# DroneMainBoard.net
KiCad netlist of a schematic drawn in EAGLE
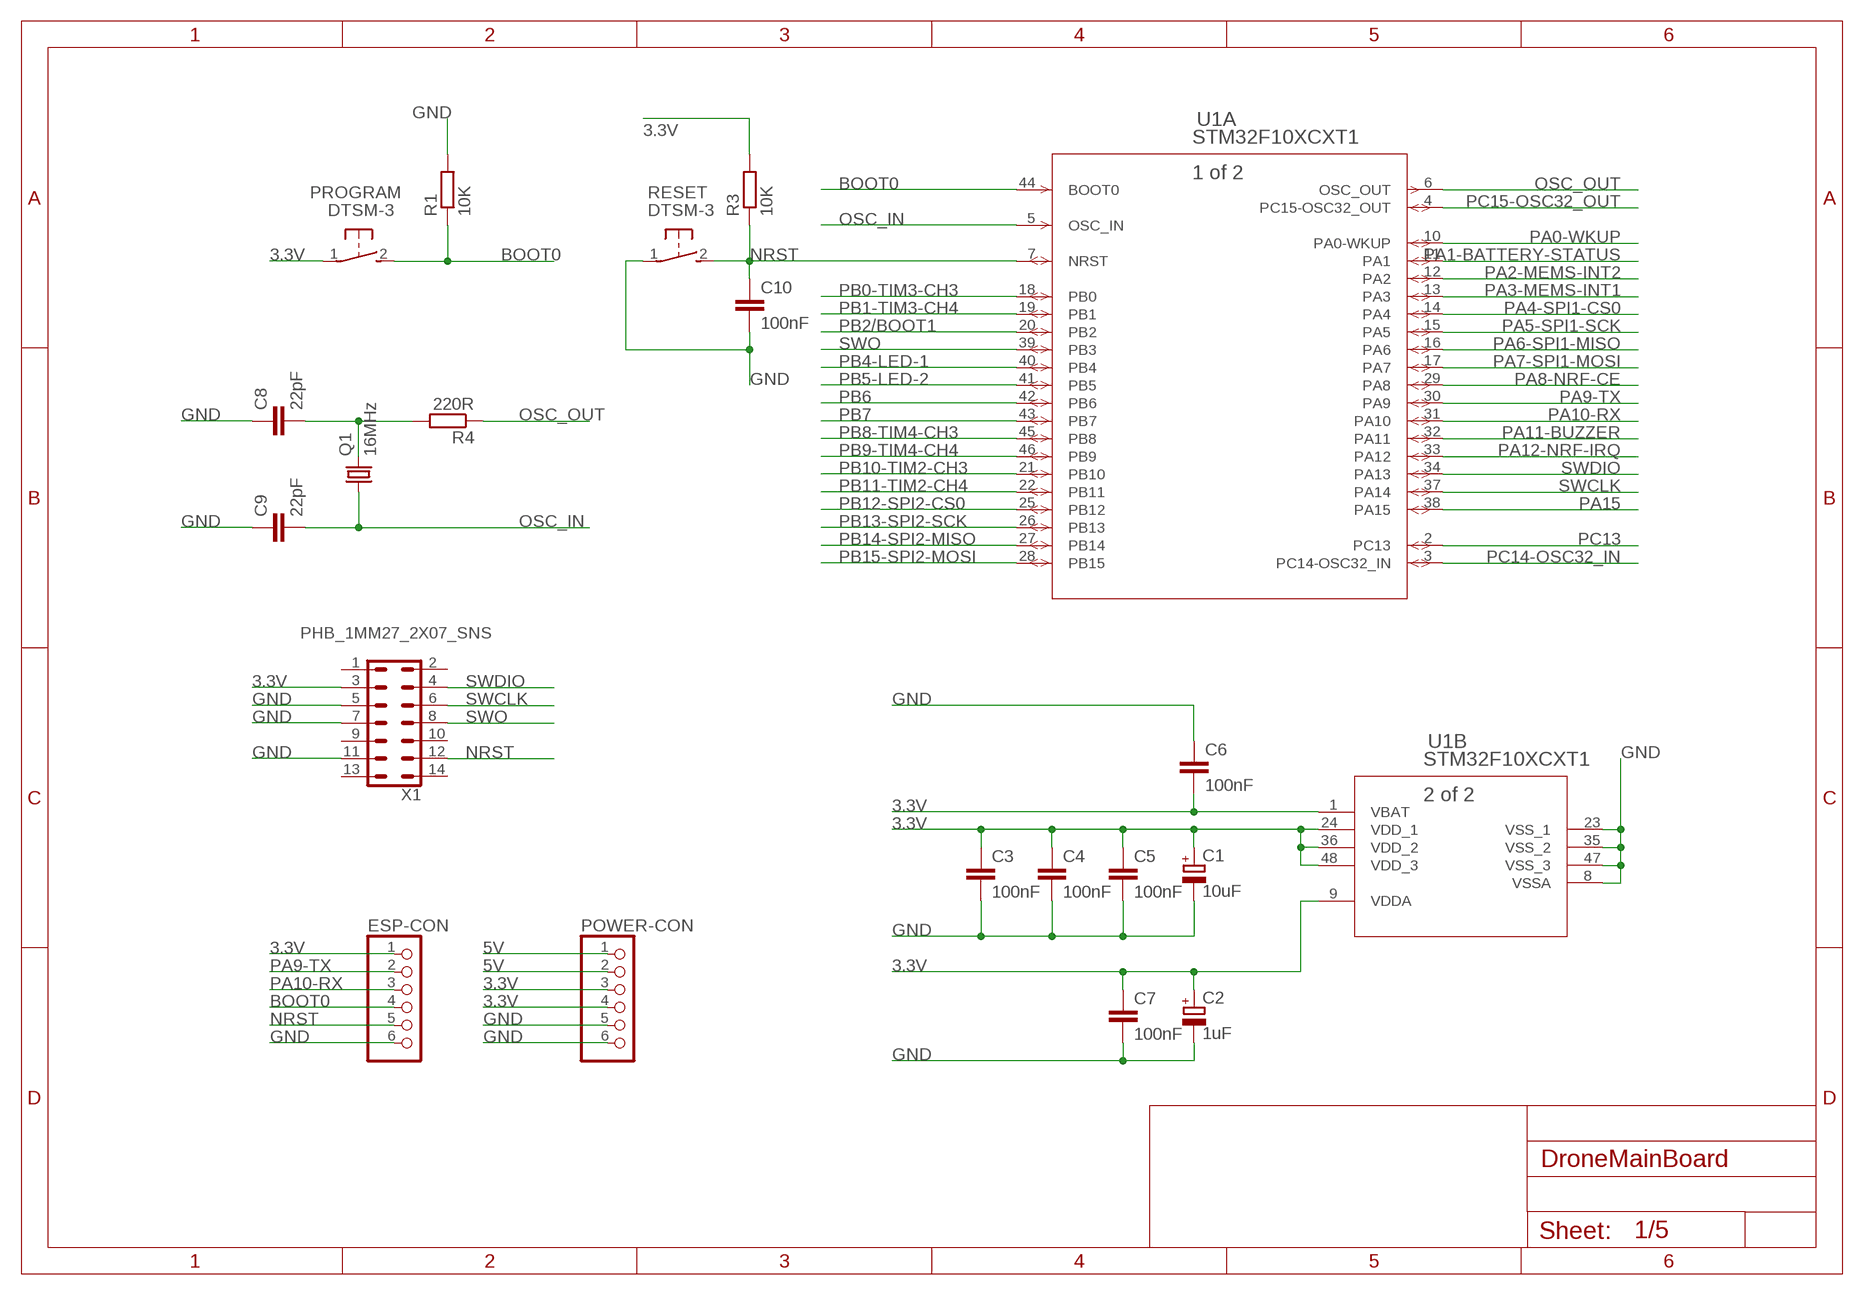
[diagram p0: schematic, sheet 1]
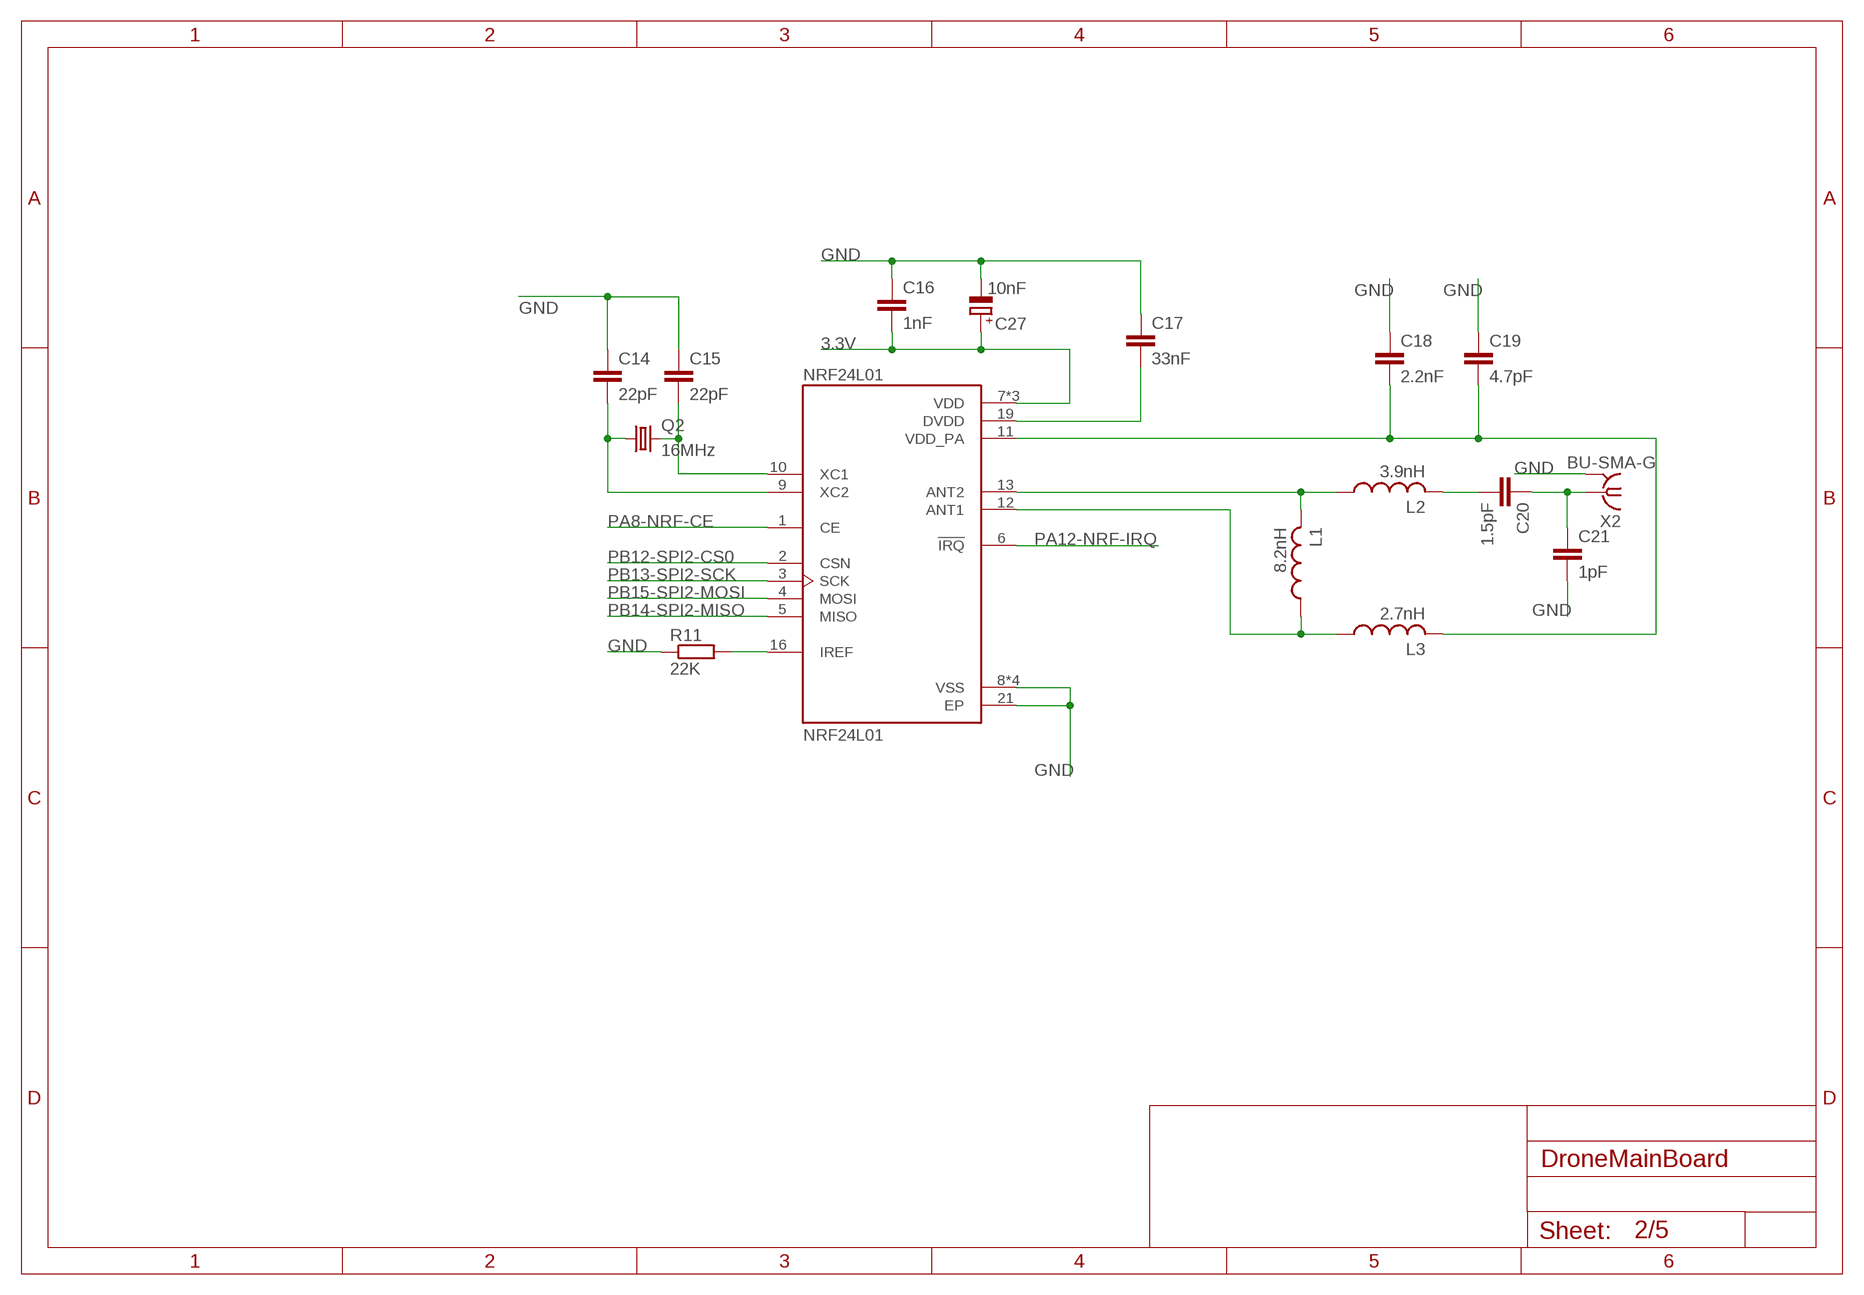
[diagram p1: schematic, sheet 2]
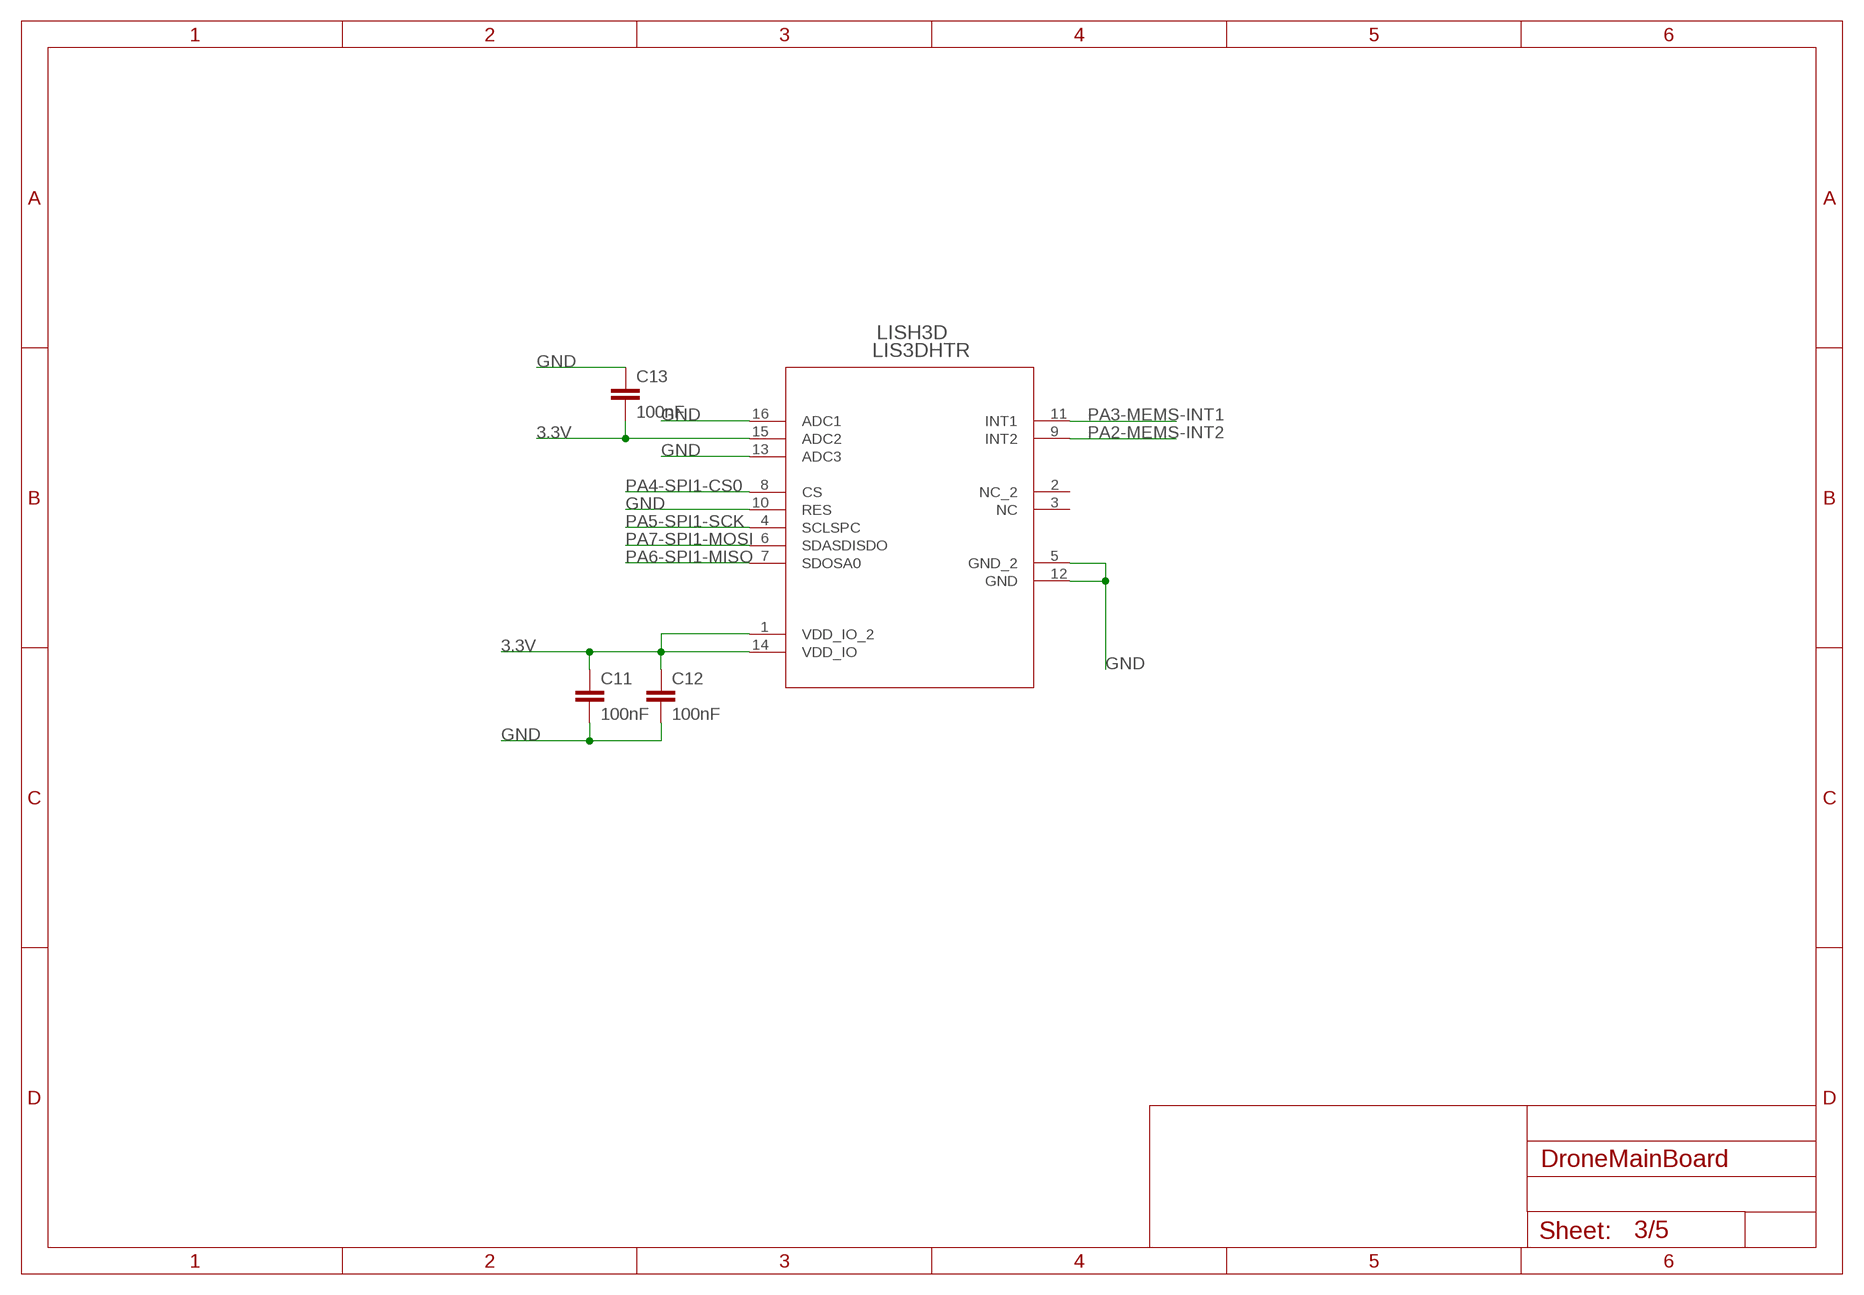
[diagram p2: schematic, sheet 3]
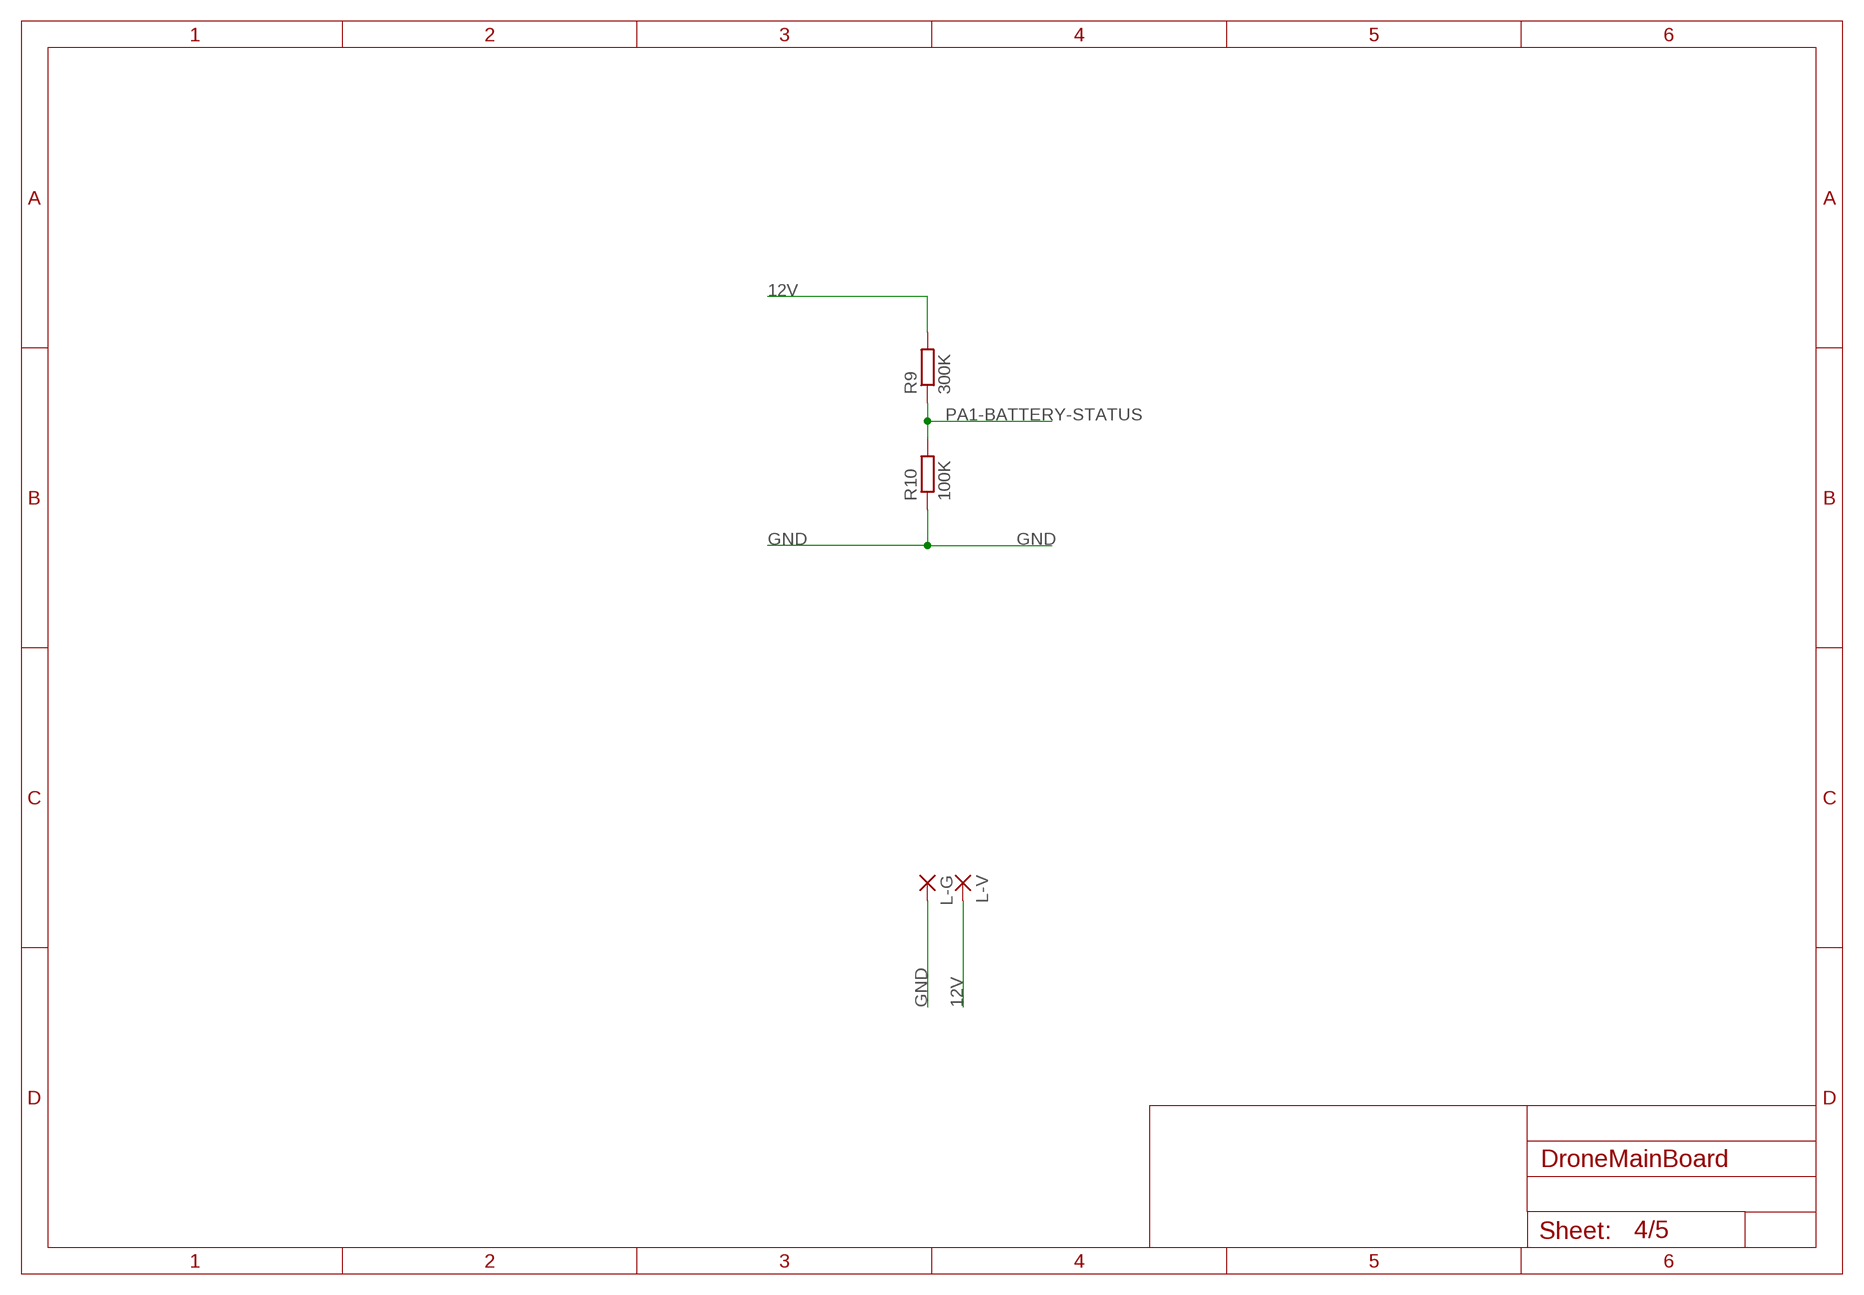
[diagram p3: schematic, sheet 4]
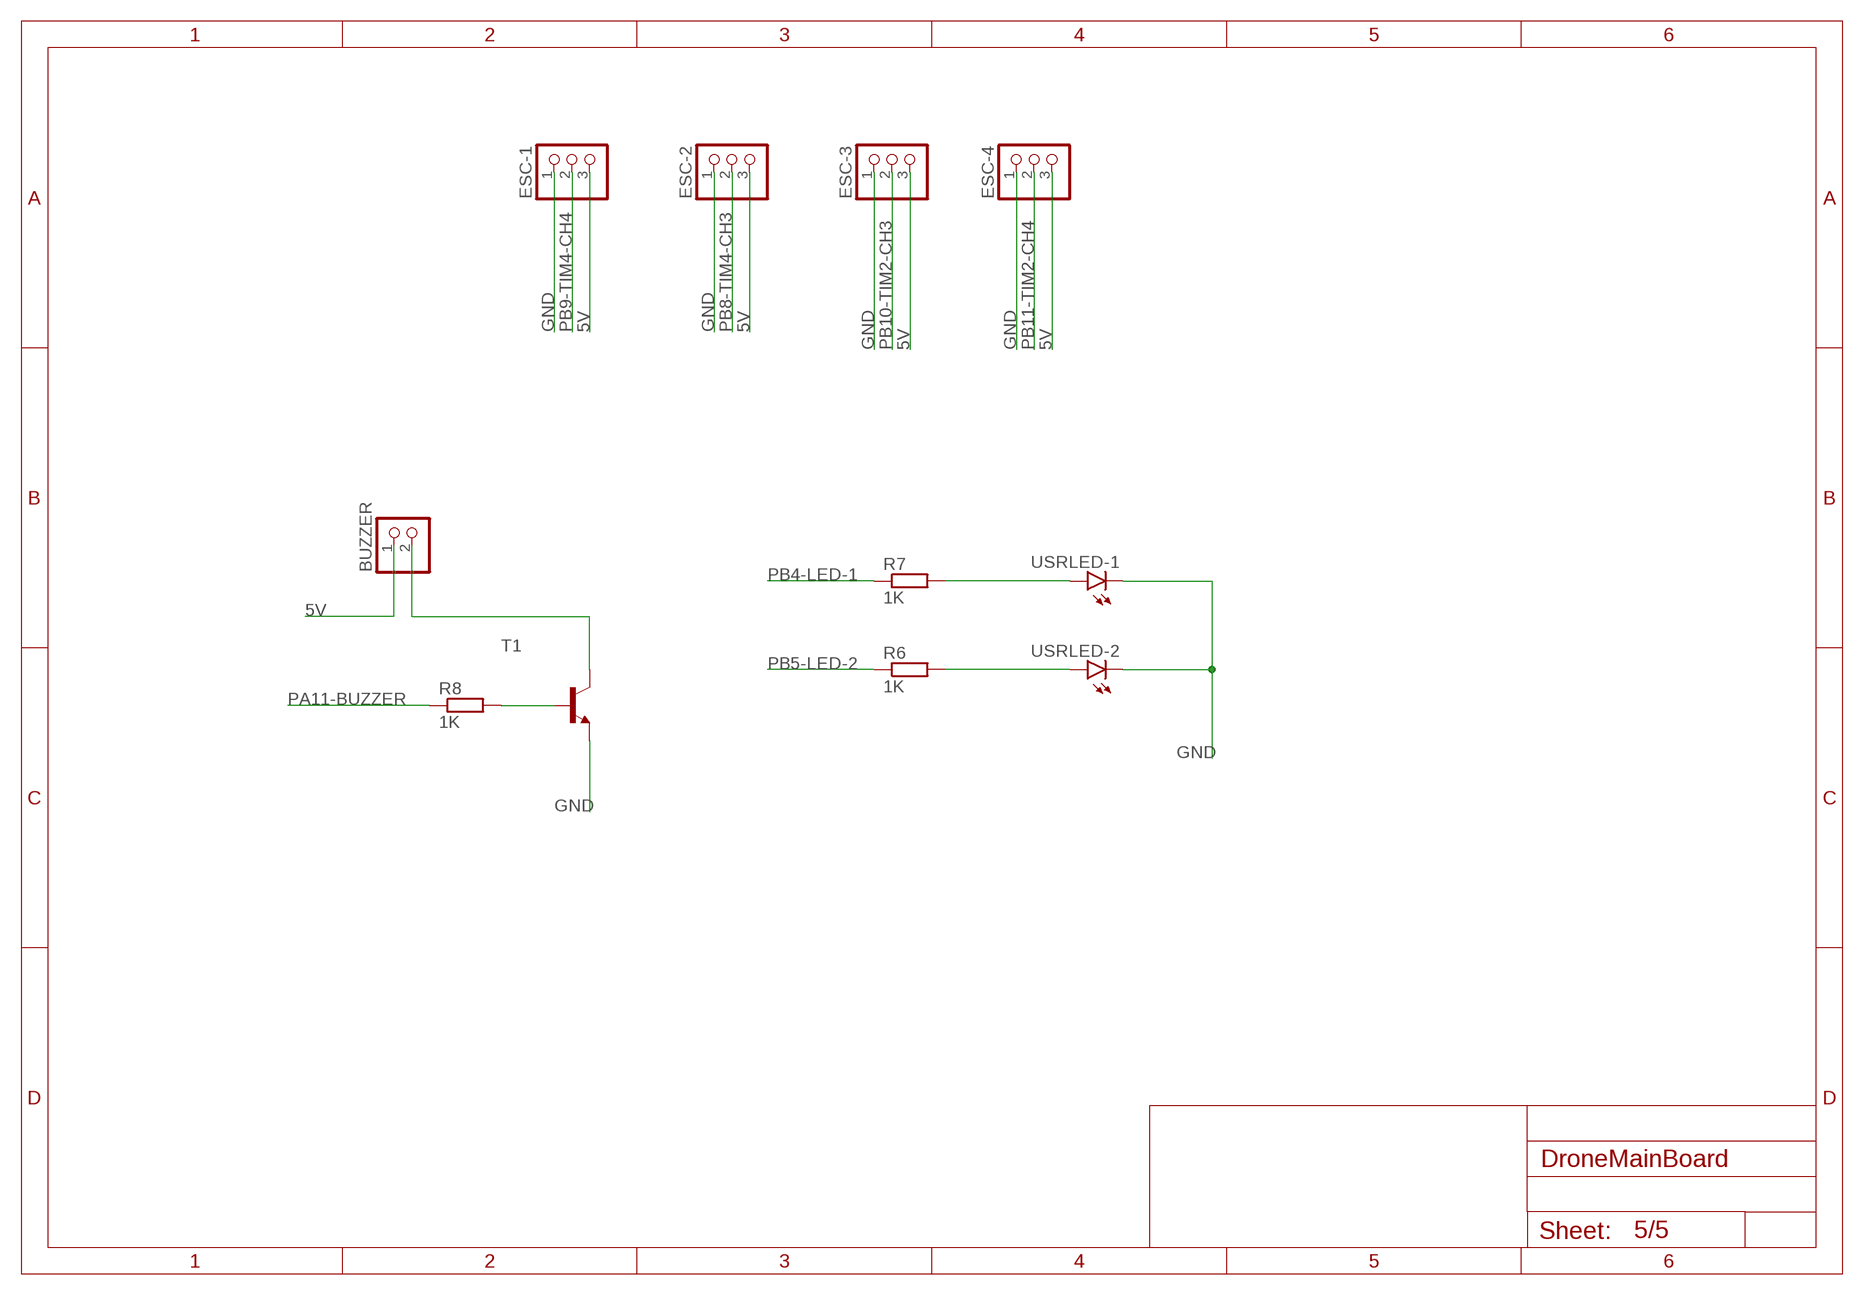
[diagram p4: schematic, sheet 5]

(export (version "E")
  (design (tool "Eeschema 10.0.6"))
  (components
    (comp (ref "C1")
      (value "10uF")
      (footprint "eagle-import:SMC_A")
      (libsource (lib "eagle-import") (part "CPOL-EUSMCA"))
    )
    (comp (ref "C2")
      (value "1uF")
      (footprint "eagle-import:SMC_A")
      (libsource (lib "eagle-import") (part "CPOL-EUSMCA"))
    )
    (comp (ref "C3")
      (value "100nF")
      (footprint "eagle-import:C0603")
      (libsource (lib "eagle-import") (part "C-EUC0603"))
    )
    (comp (ref "C4")
      (value "100nF")
      (footprint "eagle-import:C0603")
      (libsource (lib "eagle-import") (part "C-EUC0603"))
    )
    (comp (ref "C5")
      (value "100nF")
      (footprint "eagle-import:C0603")
      (libsource (lib "eagle-import") (part "C-EUC0603"))
    )
    (comp (ref "C6")
      (value "100nF")
      (footprint "eagle-import:C0603")
      (libsource (lib "eagle-import") (part "C-EUC0603"))
    )
    (comp (ref "C7")
      (value "100nF")
      (footprint "eagle-import:C0603")
      (libsource (lib "eagle-import") (part "C-EUC0603"))
    )
    (comp (ref "C8")
      (value "22pF")
      (footprint "eagle-import:C0603")
      (libsource (lib "eagle-import") (part "C-EUC0603"))
    )
    (comp (ref "C9")
      (value "22pF")
      (footprint "eagle-import:C0603")
      (libsource (lib "eagle-import") (part "C-EUC0603"))
    )
    (comp (ref "C10")
      (value "100nF")
      (footprint "eagle-import:C0603")
      (libsource (lib "eagle-import") (part "C-EUC0603"))
    )
    (comp (ref "ESP-CON")
      (value "PINHD-1X6")
      (footprint "eagle-import:1X06")
      (libsource (lib "eagle-import") (part "PINHD-1X6"))
    )
    (comp (ref "POWER-CON")
      (value "PINHD-1X6")
      (footprint "eagle-import:1X06")
      (libsource (lib "eagle-import") (part "PINHD-1X6"))
    )
    (comp (ref "PROGRAM")
      (value "DTSM-3")
      (footprint "eagle-import:DTSM-3")
      (libsource (lib "eagle-import") (part "DTSM-3"))
    )
    (comp (ref "Q1")
      (value "16MHz")
      (footprint "eagle-import:HC49_S")
      (libsource (lib "eagle-import") (part "CRYSTALHC49S"))
    )
    (comp (ref "R1")
      (value "10K")
      (footprint "eagle-import:R0603")
      (libsource (lib "eagle-import") (part "R-EU_R0603"))
    )
    (comp (ref "R3")
      (value "10K")
      (footprint "eagle-import:R0603")
      (libsource (lib "eagle-import") (part "R-EU_R0603"))
    )
    (comp (ref "R4")
      (value "220R")
      (footprint "eagle-import:R0603")
      (libsource (lib "eagle-import") (part "R-EU_R0603"))
    )
    (comp (ref "RESET")
      (value "DTSM-3")
      (footprint "eagle-import:DTSM-3")
      (libsource (lib "eagle-import") (part "DTSM-3"))
    )
    (comp (ref "U1")
      (value "STM32F10XCXT1")
      (footprint "eagle-import:LQFP48-7X7MM")
      (fields (field (name "COPYRIGHT") "Copyright (C) 2016 Accelerated Designs. All rights reserved"))
      (libsource (lib "eagle-import") (part "STM32F10XCXT1"))
    )
    (comp (ref "X1")
      (value "PHB_1MM27_2X07_SNS")
      (footprint "eagle-import:PHB_1MM27_2X07_SNS")
      (libsource (lib "eagle-import") (part "PHB_1MM27_2X07_SNS"))
    )
    (comp (ref "C11")
      (value "100nF")
      (footprint "eagle-import:C0603")
      (libsource (lib "eagle-import") (part "C-EUC0603"))
    )
    (comp (ref "C12")
      (value "100nF")
      (footprint "eagle-import:C0603")
      (libsource (lib "eagle-import") (part "C-EUC0603"))
    )
    (comp (ref "C13")
      (value "100nF")
      (footprint "eagle-import:C0603")
      (libsource (lib "eagle-import") (part "C-EUC0603"))
    )
    (comp (ref "LISH3D")
      (value "LIS3DHTR")
      (footprint "eagle-import:LGA-16_3X3X1MM_STM")
      (libsource (lib "eagle-import") (part "LIS3DHTR"))
    )
    (comp (ref "C14")
      (value "22pF")
      (footprint "eagle-import:C0603")
      (libsource (lib "eagle-import") (part "C-EUC0603"))
    )
    (comp (ref "C15")
      (value "22pF")
      (footprint "eagle-import:C0603")
      (libsource (lib "eagle-import") (part "C-EUC0603"))
    )
    (comp (ref "C16")
      (value "1nF")
      (footprint "eagle-import:C0603")
      (libsource (lib "eagle-import") (part "C-EUC0603"))
    )
    (comp (ref "C17")
      (value "33nF")
      (footprint "eagle-import:C0603")
      (libsource (lib "eagle-import") (part "C-EUC0603"))
    )
    (comp (ref "C18")
      (value "2.2nF")
      (footprint "eagle-import:C0603")
      (libsource (lib "eagle-import") (part "C-EUC0603"))
    )
    (comp (ref "C19")
      (value "4.7pF")
      (footprint "eagle-import:C0603")
      (libsource (lib "eagle-import") (part "C-EUC0603"))
    )
    (comp (ref "C20")
      (value "1.5pF")
      (footprint "eagle-import:C0603")
      (libsource (lib "eagle-import") (part "C-EUC0603"))
    )
    (comp (ref "C21")
      (value "1pF")
      (footprint "eagle-import:C0603")
      (libsource (lib "eagle-import") (part "C-EUC0603"))
    )
    (comp (ref "C27")
      (value "10nF")
      (footprint "eagle-import:SMC_A")
      (libsource (lib "eagle-import") (part "CPOL-EUSMCA"))
    )
    (comp (ref "L1")
      (value "8.2nH")
      (footprint "eagle-import:L2012C")
      (libsource (lib "eagle-import") (part "L-USL2012C"))
    )
    (comp (ref "L2")
      (value "3.9nH")
      (footprint "eagle-import:L2012C")
      (libsource (lib "eagle-import") (part "L-USL2012C"))
    )
    (comp (ref "L3")
      (value "2.7nH")
      (footprint "eagle-import:L2012C")
      (libsource (lib "eagle-import") (part "L-USL2012C"))
    )
    (comp (ref "NRF24L01")
      (value "NRF24L01")
      (footprint "eagle-import:QFN50P400X400X95-21N")
      (fields (field (name "MF") "Nordic"))
      (libsource (lib "eagle-import") (part "NRF24L01"))
    )
    (comp (ref "Q2")
      (value "16MHz")
      (footprint "eagle-import:HC49_S")
      (libsource (lib "eagle-import") (part "CRYSTALHC49S"))
    )
    (comp (ref "R11")
      (value "22K")
      (footprint "eagle-import:R0603")
      (libsource (lib "eagle-import") (part "R-EU_R0603"))
    )
    (comp (ref "X2")
      (value "BU-SMA-G")
      (footprint "eagle-import:BU-SMA-G")
      (libsource (lib "eagle-import") (part "BU-SMA-G"))
    )
    (comp (ref "L-G")
      (value "2,54/1,1")
      (footprint "eagle-import:2,54_1,1")
      (libsource (lib "eagle-import") (part "2,54/1,1"))
    )
    (comp (ref "L-V")
      (value "2,54/1,1")
      (footprint "eagle-import:2,54_1,1")
      (libsource (lib "eagle-import") (part "2,54/1,1"))
    )
    (comp (ref "R9")
      (value "300K")
      (footprint "eagle-import:R0603")
      (libsource (lib "eagle-import") (part "R-EU_R0603"))
    )
    (comp (ref "R10")
      (value "100K")
      (footprint "eagle-import:R0603")
      (libsource (lib "eagle-import") (part "R-EU_R0603"))
    )
    (comp (ref "BUZZER")
      (value "PINHD-1X2")
      (footprint "eagle-import:1X02")
      (libsource (lib "eagle-import") (part "PINHD-1X2"))
    )
    (comp (ref "ESC-1")
      (value "PINHD-1X3")
      (footprint "eagle-import:1X03")
      (libsource (lib "eagle-import") (part "PINHD-1X3"))
    )
    (comp (ref "ESC-2")
      (value "PINHD-1X3")
      (footprint "eagle-import:1X03")
      (libsource (lib "eagle-import") (part "PINHD-1X3"))
    )
    (comp (ref "ESC-3")
      (value "PINHD-1X3")
      (footprint "eagle-import:1X03")
      (libsource (lib "eagle-import") (part "PINHD-1X3"))
    )
    (comp (ref "ESC-4")
      (value "PINHD-1X3")
      (footprint "eagle-import:1X03")
      (libsource (lib "eagle-import") (part "PINHD-1X3"))
    )
    (comp (ref "R6")
      (value "1K")
      (footprint "eagle-import:R0603")
      (libsource (lib "eagle-import") (part "R-EU_R0603"))
    )
    (comp (ref "R7")
      (value "1K")
      (footprint "eagle-import:R0603")
      (libsource (lib "eagle-import") (part "R-EU_R0603"))
    )
    (comp (ref "R8")
      (value "1K")
      (footprint "eagle-import:R0603")
      (libsource (lib "eagle-import") (part "R-EU_R0603"))
    )
    (comp (ref "T1")
      (value "MMBT3904LT1-NPN-SOT23-BEC")
      (footprint "eagle-import:SOT23-BEC")
      (libsource (lib "eagle-import") (part "-NPN-SOT23-BECMMBT3904LT1"))
    )
    (comp (ref "USRLED-1")
      (value "LEDCHIP-LED0805")
      (footprint "eagle-import:CHIP-LED0805")
      (libsource (lib "eagle-import") (part "LEDCHIP-LED0805"))
    )
    (comp (ref "USRLED-2")
      (value "LEDCHIP-LED0805")
      (footprint "eagle-import:CHIP-LED0805")
      (libsource (lib "eagle-import") (part "LEDCHIP-LED0805"))
    )
  )
  (nets
    (net (code "1") (name "3.3V") (class "Default")
      (node (ref "C1") (pin "+") (pinfunction "+_+") (pintype "passive"))
      (node (ref "C11") (pin "1") (pinfunction "1_1") (pintype "passive"))
      (node (ref "C12") (pin "1") (pinfunction "1_1") (pintype "passive"))
      (node (ref "C13") (pin "2") (pinfunction "2_2") (pintype "passive"))
      (node (ref "C16") (pin "2") (pinfunction "2_2") (pintype "passive"))
      (node (ref "C2") (pin "+") (pinfunction "+_+") (pintype "passive"))
      (node (ref "C27") (pin "+") (pinfunction "+_+") (pintype "passive"))
      (node (ref "C3") (pin "1") (pinfunction "1_1") (pintype "passive"))
      (node (ref "C4") (pin "1") (pinfunction "1_1") (pintype "passive"))
      (node (ref "C5") (pin "1") (pinfunction "1_1") (pintype "passive"))
      (node (ref "C6") (pin "2") (pinfunction "2_2") (pintype "passive"))
      (node (ref "C7") (pin "1") (pinfunction "1_1") (pintype "passive"))
      (node (ref "ESP-CON") (pin "1") (pinfunction "1_1") (pintype "passive"))
      (node (ref "LISH3D") (pin "1") (pinfunction "VDD_IO_2_1") (pintype "power_in"))
      (node (ref "LISH3D") (pin "14") (pinfunction "VDD_IO_14") (pintype "power_in"))
      (node (ref "LISH3D") (pin "15") (pinfunction "ADC2_15") (pintype "input"))
      (node (ref "NRF24L01") (pin "15") (pinfunction "VDD_15") (pintype "power_in"))
      (node (ref "NRF24L01") (pin "18") (pinfunction "VDD_18") (pintype "power_in"))
      (node (ref "NRF24L01") (pin "7") (pinfunction "VDD_7") (pintype "power_in"))
      (node (ref "POWER-CON") (pin "3") (pinfunction "3_3") (pintype "passive"))
      (node (ref "POWER-CON") (pin "4") (pinfunction "4_4") (pintype "passive"))
      (node (ref "PROGRAM") (pin "1") (pinfunction "1_1") (pintype "passive"))
      (node (ref "R3") (pin "2") (pinfunction "2_2") (pintype "passive"))
      (node (ref "U1") (pin "1") (pinfunction "VBAT_1") (pintype "power_in"))
      (node (ref "U1") (pin "24") (pinfunction "VDD_1_24") (pintype "power_in"))
      (node (ref "U1") (pin "36") (pinfunction "VDD_2_36") (pintype "power_in"))
      (node (ref "U1") (pin "48") (pinfunction "VDD_3_48") (pintype "power_in"))
      (node (ref "U1") (pin "9") (pinfunction "VDDA_9") (pintype "power_in"))
      (node (ref "X1") (pin "3") (pinfunction "3_3") (pintype "passive"))
    )
    (net (code "2") (name "5V") (class "Default")
      (node (ref "BUZZER") (pin "1") (pinfunction "1_1") (pintype "passive"))
      (node (ref "ESC-1") (pin "3") (pinfunction "3_3") (pintype "passive"))
      (node (ref "ESC-2") (pin "3") (pinfunction "3_3") (pintype "passive"))
      (node (ref "ESC-3") (pin "3") (pinfunction "3_3") (pintype "passive"))
      (node (ref "ESC-4") (pin "3") (pinfunction "3_3") (pintype "passive"))
      (node (ref "POWER-CON") (pin "1") (pinfunction "1_1") (pintype "passive"))
      (node (ref "POWER-CON") (pin "2") (pinfunction "2_2") (pintype "passive"))
    )
    (net (code "3") (name "12V") (class "Default")
      (node (ref "L-V") (pin "1") (pinfunction "P_1") (pintype "passive"))
      (node (ref "R9") (pin "2") (pinfunction "2_2") (pintype "passive"))
    )
    (net (code "4") (name "BOOT0") (class "Default")
      (node (ref "ESP-CON") (pin "4") (pinfunction "4_4") (pintype "passive"))
      (node (ref "PROGRAM") (pin "2") (pinfunction "2_2") (pintype "passive"))
      (node (ref "R1") (pin "1") (pinfunction "1_1") (pintype "passive"))
      (node (ref "U1") (pin "44") (pinfunction "BOOT0_44") (pintype "input"))
    )
    (net (code "5") (name "GND") (class "Default")
      (node (ref "C1") (pin "-") (pinfunction "-_-") (pintype "passive"))
      (node (ref "C10") (pin "2") (pinfunction "2_2") (pintype "passive"))
      (node (ref "C11") (pin "2") (pinfunction "2_2") (pintype "passive"))
      (node (ref "C12") (pin "2") (pinfunction "2_2") (pintype "passive"))
      (node (ref "C13") (pin "1") (pinfunction "1_1") (pintype "passive"))
      (node (ref "C14") (pin "1") (pinfunction "1_1") (pintype "passive"))
      (node (ref "C15") (pin "1") (pinfunction "1_1") (pintype "passive"))
      (node (ref "C16") (pin "1") (pinfunction "1_1") (pintype "passive"))
      (node (ref "C17") (pin "1") (pinfunction "1_1") (pintype "passive"))
      (node (ref "C18") (pin "1") (pinfunction "1_1") (pintype "passive"))
      (node (ref "C19") (pin "1") (pinfunction "1_1") (pintype "passive"))
      (node (ref "C2") (pin "-") (pinfunction "-_-") (pintype "passive"))
      (node (ref "C21") (pin "2") (pinfunction "2_2") (pintype "passive"))
      (node (ref "C27") (pin "-") (pinfunction "-_-") (pintype "passive"))
      (node (ref "C3") (pin "2") (pinfunction "2_2") (pintype "passive"))
      (node (ref "C4") (pin "2") (pinfunction "2_2") (pintype "passive"))
      (node (ref "C5") (pin "2") (pinfunction "2_2") (pintype "passive"))
      (node (ref "C6") (pin "1") (pinfunction "1_1") (pintype "passive"))
      (node (ref "C7") (pin "2") (pinfunction "2_2") (pintype "passive"))
      (node (ref "C8") (pin "1") (pinfunction "1_1") (pintype "passive"))
      (node (ref "C9") (pin "1") (pinfunction "1_1") (pintype "passive"))
      (node (ref "ESC-1") (pin "1") (pinfunction "1_1") (pintype "passive"))
      (node (ref "ESC-2") (pin "1") (pinfunction "1_1") (pintype "passive"))
      (node (ref "ESC-3") (pin "1") (pinfunction "1_1") (pintype "passive"))
      (node (ref "ESC-4") (pin "1") (pinfunction "1_1") (pintype "passive"))
      (node (ref "ESP-CON") (pin "6") (pinfunction "6_6") (pintype "passive"))
      (node (ref "L-G") (pin "1") (pinfunction "P_1") (pintype "passive"))
      (node (ref "LISH3D") (pin "10") (pinfunction "RES_10") (pintype "passive"))
      (node (ref "LISH3D") (pin "12") (pinfunction "GND_12") (pintype "power_in"))
      (node (ref "LISH3D") (pin "13") (pinfunction "ADC3_13") (pintype "input"))
      (node (ref "LISH3D") (pin "16") (pinfunction "ADC1_16") (pintype "input"))
      (node (ref "LISH3D") (pin "5") (pinfunction "GND_2_5") (pintype "power_in"))
      (node (ref "NRF24L01") (pin "14") (pinfunction "VSS_14") (pintype "power_in"))
      (node (ref "NRF24L01") (pin "17") (pinfunction "VSS_17") (pintype "power_in"))
      (node (ref "NRF24L01") (pin "20") (pinfunction "VSS_20") (pintype "power_in"))
      (node (ref "NRF24L01") (pin "21") (pinfunction "EP_21") (pintype "power_in"))
      (node (ref "NRF24L01") (pin "8") (pinfunction "VSS_8") (pintype "power_in"))
      (node (ref "POWER-CON") (pin "5") (pinfunction "5_5") (pintype "passive"))
      (node (ref "POWER-CON") (pin "6") (pinfunction "6_6") (pintype "passive"))
      (node (ref "R1") (pin "2") (pinfunction "2_2") (pintype "passive"))
      (node (ref "R10") (pin "1") (pinfunction "1_1") (pintype "passive"))
      (node (ref "R11") (pin "1") (pinfunction "1_1") (pintype "passive"))
      (node (ref "RESET") (pin "1") (pinfunction "1_1") (pintype "passive"))
      (node (ref "T1") (pin "E") (pinfunction "E_E") (pintype "passive"))
      (node (ref "U1") (pin "23") (pinfunction "VSS_1_23") (pintype "power_in"))
      (node (ref "U1") (pin "35") (pinfunction "VSS_2_35") (pintype "power_in"))
      (node (ref "U1") (pin "47") (pinfunction "VSS_3_47") (pintype "power_in"))
      (node (ref "U1") (pin "8") (pinfunction "VSSA_8") (pintype "power_in"))
      (node (ref "USRLED-1") (pin "C") (pinfunction "C_C") (pintype "passive"))
      (node (ref "USRLED-2") (pin "C") (pinfunction "C_C") (pintype "passive"))
      (node (ref "X1") (pin "11") (pinfunction "11_11") (pintype "passive"))
      (node (ref "X1") (pin "5") (pinfunction "5_5") (pintype "passive"))
      (node (ref "X1") (pin "7") (pinfunction "7_7") (pintype "passive"))
      (node (ref "X2") (pin "2") (pinfunction "2_2") (pintype "passive"))
      (node (ref "X2") (pin "3") (pinfunction "2_3") (pintype "passive"))
      (node (ref "X2") (pin "4") (pinfunction "2_4") (pintype "passive"))
      (node (ref "X2") (pin "5") (pinfunction "2_5") (pintype "passive"))
    )
    (net (code "6") (name "NRST") (class "Default")
      (node (ref "C10") (pin "1") (pinfunction "1_1") (pintype "passive"))
      (node (ref "ESP-CON") (pin "5") (pinfunction "5_5") (pintype "passive"))
      (node (ref "R3") (pin "1") (pinfunction "1_1") (pintype "passive"))
      (node (ref "RESET") (pin "2") (pinfunction "2_2") (pintype "passive"))
      (node (ref "U1") (pin "7") (pinfunction "NRST_7") (pintype "bidirectional"))
      (node (ref "X1") (pin "12") (pinfunction "12_12") (pintype "passive"))
    )
    (net (code "7") (name "Net-(BUZZER-Pad2)") (class "Default")
      (node (ref "BUZZER") (pin "2") (pinfunction "2_2") (pintype "passive"))
      (node (ref "T1") (pin "C") (pinfunction "C_C") (pintype "passive"))
    )
    (net (code "8") (name "Net-(C8-Pad2)") (class "Default")
      (node (ref "C8") (pin "2") (pinfunction "2_2") (pintype "passive"))
      (node (ref "Q1") (pin "2") (pinfunction "2_2") (pintype "passive"))
      (node (ref "R4") (pin "2") (pinfunction "2_2") (pintype "passive"))
    )
    (net (code "9") (name "Net-(C20-Pad1)") (class "Default")
      (node (ref "C20") (pin "1") (pinfunction "1_1") (pintype "passive"))
      (node (ref "C21") (pin "1") (pinfunction "1_1") (pintype "passive"))
      (node (ref "X2") (pin "1") (pinfunction "1_1") (pintype "passive"))
    )
    (net (code "10") (name "Net-(C20-Pad2)") (class "Default")
      (node (ref "C20") (pin "2") (pinfunction "2_2") (pintype "passive"))
      (node (ref "L2") (pin "2") (pinfunction "2_2") (pintype "passive"))
    )
    (net (code "11") (name "Net-(NRF24L01-ANT1)") (class "Default")
      (node (ref "L1") (pin "1") (pinfunction "1_1") (pintype "passive"))
      (node (ref "L3") (pin "1") (pinfunction "1_1") (pintype "passive"))
      (node (ref "NRF24L01") (pin "12") (pinfunction "ANT1_12") (pintype "bidirectional"))
    )
    (net (code "12") (name "Net-(NRF24L01-ANT2)") (class "Default")
      (node (ref "L1") (pin "2") (pinfunction "2_2") (pintype "passive"))
      (node (ref "L2") (pin "1") (pinfunction "1_1") (pintype "passive"))
      (node (ref "NRF24L01") (pin "13") (pinfunction "ANT2_13") (pintype "bidirectional"))
    )
    (net (code "13") (name "Net-(NRF24L01-DVDD)") (class "Default")
      (node (ref "C17") (pin "2") (pinfunction "2_2") (pintype "passive"))
      (node (ref "NRF24L01") (pin "19") (pinfunction "DVDD_19") (pintype "power_in"))
    )
    (net (code "14") (name "Net-(NRF24L01-IREF)") (class "Default")
      (node (ref "NRF24L01") (pin "16") (pinfunction "IREF_16") (pintype "input"))
      (node (ref "R11") (pin "2") (pinfunction "2_2") (pintype "passive"))
    )
    (net (code "15") (name "Net-(NRF24L01-VDD_PA)") (class "Default")
      (node (ref "C18") (pin "2") (pinfunction "2_2") (pintype "passive"))
      (node (ref "C19") (pin "2") (pinfunction "2_2") (pintype "passive"))
      (node (ref "L3") (pin "2") (pinfunction "2_2") (pintype "passive"))
      (node (ref "NRF24L01") (pin "11") (pinfunction "VDD_PA_11") (pintype "power_in"))
    )
    (net (code "16") (name "Net-(NRF24L01-XC1)") (class "Default")
      (node (ref "C15") (pin "2") (pinfunction "2_2") (pintype "passive"))
      (node (ref "NRF24L01") (pin "10") (pinfunction "XC1_10") (pintype "input"))
      (node (ref "Q2") (pin "2") (pinfunction "2_2") (pintype "passive"))
    )
    (net (code "17") (name "Net-(NRF24L01-XC2)") (class "Default")
      (node (ref "C14") (pin "2") (pinfunction "2_2") (pintype "passive"))
      (node (ref "NRF24L01") (pin "9") (pinfunction "XC2_9") (pintype "output"))
      (node (ref "Q2") (pin "1") (pinfunction "1_1") (pintype "passive"))
    )
    (net (code "18") (name "Net-(R6-Pad2)") (class "Default")
      (node (ref "R6") (pin "2") (pinfunction "2_2") (pintype "passive"))
      (node (ref "USRLED-2") (pin "A") (pinfunction "A_A") (pintype "passive"))
    )
    (net (code "19") (name "Net-(R7-Pad2)") (class "Default")
      (node (ref "R7") (pin "2") (pinfunction "2_2") (pintype "passive"))
      (node (ref "USRLED-1") (pin "A") (pinfunction "A_A") (pintype "passive"))
    )
    (net (code "20") (name "Net-(R8-Pad2)") (class "Default")
      (node (ref "R8") (pin "2") (pinfunction "2_2") (pintype "passive"))
      (node (ref "T1") (pin "B") (pinfunction "B_B") (pintype "passive"))
    )
    (net (code "21") (name "OSC_IN") (class "Default")
      (node (ref "C9") (pin "2") (pinfunction "2_2") (pintype "passive"))
      (node (ref "Q1") (pin "1") (pinfunction "1_1") (pintype "passive"))
      (node (ref "U1") (pin "5") (pinfunction "OSC_IN_5") (pintype "input"))
    )
    (net (code "22") (name "OSC_OUT") (class "Default")
      (node (ref "R4") (pin "1") (pinfunction "1_1") (pintype "passive"))
      (node (ref "U1") (pin "6") (pinfunction "OSC_OUT_6") (pintype "output"))
    )
    (net (code "23") (name "PA0-WKUP") (class "Default")
      (node (ref "U1") (pin "10") (pinfunction "PA0-WKUP_10") (pintype "bidirectional"))
    )
    (net (code "24") (name "PA1-BATTERY-STATUS") (class "Default")
      (node (ref "R10") (pin "2") (pinfunction "2_2") (pintype "passive"))
      (node (ref "R9") (pin "1") (pinfunction "1_1") (pintype "passive"))
      (node (ref "U1") (pin "11") (pinfunction "PA1_11") (pintype "bidirectional"))
    )
    (net (code "25") (name "PA2-MEMS-INT2") (class "Default")
      (node (ref "LISH3D") (pin "9") (pinfunction "INT2_9") (pintype "passive"))
      (node (ref "U1") (pin "12") (pinfunction "PA2_12") (pintype "bidirectional"))
    )
    (net (code "26") (name "PA3-MEMS-INT1") (class "Default")
      (node (ref "LISH3D") (pin "11") (pinfunction "INT1_11") (pintype "passive"))
      (node (ref "U1") (pin "13") (pinfunction "PA3_13") (pintype "bidirectional"))
    )
    (net (code "27") (name "PA4-SPI1-CS0") (class "Default")
      (node (ref "LISH3D") (pin "8") (pinfunction "CS_8") (pintype "passive"))
      (node (ref "U1") (pin "14") (pinfunction "PA4_14") (pintype "bidirectional"))
    )
    (net (code "28") (name "PA5-SPI1-SCK") (class "Default")
      (node (ref "LISH3D") (pin "4") (pinfunction "SCLSPC_4") (pintype "passive"))
      (node (ref "U1") (pin "15") (pinfunction "PA5_15") (pintype "bidirectional"))
    )
    (net (code "29") (name "PA6-SPI1-MISO") (class "Default")
      (node (ref "LISH3D") (pin "7") (pinfunction "SDOSA0_7") (pintype "passive"))
      (node (ref "U1") (pin "16") (pinfunction "PA6_16") (pintype "bidirectional"))
    )
    (net (code "30") (name "PA7-SPI1-MOSI") (class "Default")
      (node (ref "LISH3D") (pin "6") (pinfunction "SDASDISDO_6") (pintype "passive"))
      (node (ref "U1") (pin "17") (pinfunction "PA7_17") (pintype "bidirectional"))
    )
    (net (code "31") (name "PA8-NRF-CE") (class "Default")
      (node (ref "NRF24L01") (pin "1") (pinfunction "CE_1") (pintype "input"))
      (node (ref "U1") (pin "29") (pinfunction "PA8_29") (pintype "bidirectional"))
    )
    (net (code "32") (name "PA9-TX") (class "Default")
      (node (ref "ESP-CON") (pin "2") (pinfunction "2_2") (pintype "passive"))
      (node (ref "U1") (pin "30") (pinfunction "PA9_30") (pintype "bidirectional"))
    )
    (net (code "33") (name "PA10-RX") (class "Default")
      (node (ref "ESP-CON") (pin "3") (pinfunction "3_3") (pintype "passive"))
      (node (ref "U1") (pin "31") (pinfunction "PA10_31") (pintype "bidirectional"))
    )
    (net (code "34") (name "PA11-BUZZER") (class "Default")
      (node (ref "R8") (pin "1") (pinfunction "1_1") (pintype "passive"))
      (node (ref "U1") (pin "32") (pinfunction "PA11_32") (pintype "bidirectional"))
    )
    (net (code "35") (name "PA12-NRF-IRQ") (class "Default")
      (node (ref "NRF24L01") (pin "6") (pinfunction "~{IRQ}_6") (pintype "output"))
      (node (ref "U1") (pin "33") (pinfunction "PA12_33") (pintype "bidirectional"))
    )
    (net (code "36") (name "PA15") (class "Default")
      (node (ref "U1") (pin "38") (pinfunction "PA15_38") (pintype "bidirectional"))
    )
    (net (code "37") (name "PB0-TIM3-CH3") (class "Default")
      (node (ref "U1") (pin "18") (pinfunction "PB0_18") (pintype "bidirectional"))
    )
    (net (code "38") (name "PB1-TIM3-CH4") (class "Default")
      (node (ref "U1") (pin "19") (pinfunction "PB1_19") (pintype "bidirectional"))
    )
    (net (code "39") (name "PB2{slash}BOOT1") (class "Default")
      (node (ref "U1") (pin "20") (pinfunction "PB2_20") (pintype "bidirectional"))
    )
    (net (code "40") (name "PB4-LED-1") (class "Default")
      (node (ref "R7") (pin "1") (pinfunction "1_1") (pintype "passive"))
      (node (ref "U1") (pin "40") (pinfunction "PB4_40") (pintype "bidirectional"))
    )
    (net (code "41") (name "PB5-LED-2") (class "Default")
      (node (ref "R6") (pin "1") (pinfunction "1_1") (pintype "passive"))
      (node (ref "U1") (pin "41") (pinfunction "PB5_41") (pintype "bidirectional"))
    )
    (net (code "42") (name "PB6") (class "Default")
      (node (ref "U1") (pin "42") (pinfunction "PB6_42") (pintype "bidirectional"))
    )
    (net (code "43") (name "PB7") (class "Default")
      (node (ref "U1") (pin "43") (pinfunction "PB7_43") (pintype "bidirectional"))
    )
    (net (code "44") (name "PB8-TIM4-CH3") (class "Default")
      (node (ref "ESC-2") (pin "2") (pinfunction "2_2") (pintype "passive"))
      (node (ref "U1") (pin "45") (pinfunction "PB8_45") (pintype "bidirectional"))
    )
    (net (code "45") (name "PB9-TIM4-CH4") (class "Default")
      (node (ref "ESC-1") (pin "2") (pinfunction "2_2") (pintype "passive"))
      (node (ref "U1") (pin "46") (pinfunction "PB9_46") (pintype "bidirectional"))
    )
    (net (code "46") (name "PB10-TIM2-CH3") (class "Default")
      (node (ref "ESC-3") (pin "2") (pinfunction "2_2") (pintype "passive"))
      (node (ref "U1") (pin "21") (pinfunction "PB10_21") (pintype "bidirectional"))
    )
    (net (code "47") (name "PB11-TIM2-CH4") (class "Default")
      (node (ref "ESC-4") (pin "2") (pinfunction "2_2") (pintype "passive"))
      (node (ref "U1") (pin "22") (pinfunction "PB11_22") (pintype "bidirectional"))
    )
    (net (code "48") (name "PB12-SPI2-CS0") (class "Default")
      (node (ref "NRF24L01") (pin "2") (pinfunction "CSN_2") (pintype "input"))
      (node (ref "U1") (pin "25") (pinfunction "PB12_25") (pintype "bidirectional"))
    )
    (net (code "49") (name "PB13-SPI2-SCK") (class "Default")
      (node (ref "NRF24L01") (pin "3") (pinfunction "SCK_3") (pintype "input"))
      (node (ref "U1") (pin "26") (pinfunction "PB13_26") (pintype "bidirectional"))
    )
    (net (code "50") (name "PB14-SPI2-MISO") (class "Default")
      (node (ref "NRF24L01") (pin "5") (pinfunction "MISO_5") (pintype "output"))
      (node (ref "U1") (pin "27") (pinfunction "PB14_27") (pintype "bidirectional"))
    )
    (net (code "51") (name "PB15-SPI2-MOSI") (class "Default")
      (node (ref "NRF24L01") (pin "4") (pinfunction "MOSI_4") (pintype "input"))
      (node (ref "U1") (pin "28") (pinfunction "PB15_28") (pintype "bidirectional"))
    )
    (net (code "52") (name "PC13") (class "Default")
      (node (ref "U1") (pin "2") (pinfunction "PC13_2") (pintype "bidirectional"))
    )
    (net (code "53") (name "PC14-OSC32_IN") (class "Default")
      (node (ref "U1") (pin "3") (pinfunction "PC14-OSC32_IN_3") (pintype "bidirectional"))
    )
    (net (code "54") (name "PC15-OSC32_OUT") (class "Default")
      (node (ref "U1") (pin "4") (pinfunction "PC15-OSC32_OUT_4") (pintype "bidirectional"))
    )
    (net (code "55") (name "SWCLK") (class "Default")
      (node (ref "U1") (pin "37") (pinfunction "PA14_37") (pintype "bidirectional"))
      (node (ref "X1") (pin "6") (pinfunction "6_6") (pintype "passive"))
    )
    (net (code "56") (name "SWDIO") (class "Default")
      (node (ref "U1") (pin "34") (pinfunction "PA13_34") (pintype "bidirectional"))
      (node (ref "X1") (pin "4") (pinfunction "4_4") (pintype "passive"))
    )
    (net (code "57") (name "SWO") (class "Default")
      (node (ref "U1") (pin "39") (pinfunction "PB3_39") (pintype "bidirectional"))
      (node (ref "X1") (pin "8") (pinfunction "8_8") (pintype "passive"))
    )
    (net (code "58") (name "unconnected-(LISH3D-NC-Pad3)") (class "Default")
      (node (ref "LISH3D") (pin "3") (pinfunction "NC_3") (pintype "no_connect"))
    )
    (net (code "59") (name "unconnected-(LISH3D-NC_2-Pad2)") (class "Default")
      (node (ref "LISH3D") (pin "2") (pinfunction "NC_2_2") (pintype "no_connect"))
    )
    (net (code "60") (name "unconnected-(X1-Pad1)") (class "Default")
      (node (ref "X1") (pin "1") (pinfunction "1_1") (pintype "passive"))
    )
    (net (code "61") (name "unconnected-(X1-Pad2)") (class "Default")
      (node (ref "X1") (pin "2") (pinfunction "2_2") (pintype "passive"))
    )
    (net (code "62") (name "unconnected-(X1-Pad9)") (class "Default")
      (node (ref "X1") (pin "9") (pinfunction "9_9") (pintype "passive"))
    )
    (net (code "63") (name "unconnected-(X1-Pad10)") (class "Default")
      (node (ref "X1") (pin "10") (pinfunction "10_10") (pintype "passive"))
    )
    (net (code "64") (name "unconnected-(X1-Pad13)") (class "Default")
      (node (ref "X1") (pin "13") (pinfunction "13_13") (pintype "passive"))
    )
    (net (code "65") (name "unconnected-(X1-Pad14)") (class "Default")
      (node (ref "X1") (pin "14") (pinfunction "14_14") (pintype "passive"))
    )
  )
)
